# 5V_Converter.net
KiCad netlist of a schematic drawn in Altium Designer
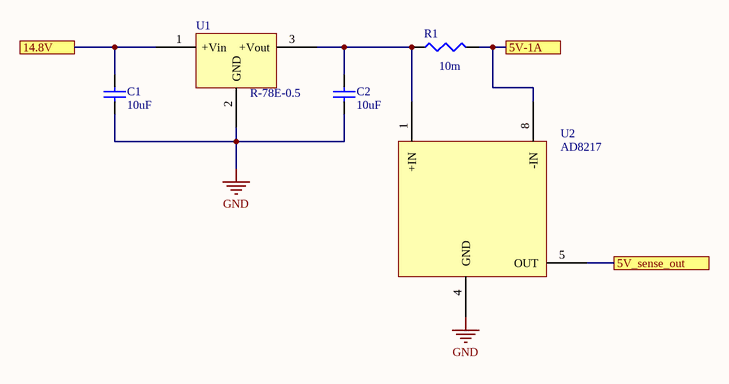
[diagram p0: 5V_Converter.SchDoc]

(export (version "E")
  (design (tool "Eeschema 10.0.6"))
  (components
    (comp (ref "C1")
      (value "10uF")
      (footprint "C1206")
      (description "Capacitor (Semiconductor SIM Model)")
      (fields (field (name "PUBLISHER") "Altium Limited"))
      (libsource (lib "Miscellaneous Devices") (part "Cap Semi"))
    )
    (comp (ref "C2")
      (value "10uF")
      (footprint "C1206")
      (description "Capacitor (Semiconductor SIM Model)")
      (fields (field (name "PUBLISHER") "Altium Limited"))
      (libsource (lib "Miscellaneous Devices") (part "Cap Semi"))
    )
    (comp (ref "R1")
      (value "10m")
      (footprint "J1-0603")
      (description "Resistor")
      (fields (field (name "Comment") "Res3") (field (name "PUBLISHER") "Altium Limited"))
      (libsource (lib "Miscellaneous Devices") (part "Res3"))
    )
    (comp (ref "U1")
      (value "R-78E-0.5")
      (footprint "R-78E-0.5")
      (description "DC/DC Converter")
      (libsource (lib "Integrated_Library") (part "R-78E-0.5"))
    )
    (comp (ref "U2")
      (value "AD8217")
      (footprint "AD8217")
      (description "Current Shunt Moniter")
      (libsource (lib "Integrated_Library") (part "AD8217"))
    )
  )
  (nets
    (net (code "1") (name "/5V-1A") (class "Default")
      (node (ref "R1") (pin "2") (pinfunction "2_2") (pintype "passive"))
      (node (ref "U2") (pin "8") (pinfunction "-IN_8") (pintype "passive"))
    )
    (net (code "2") (name "/5V_sense_out") (class "Default")
      (node (ref "U2") (pin "5") (pinfunction "OUT_5") (pintype "passive"))
    )
    (net (code "3") (name "/14.8V") (class "Default")
      (node (ref "C1") (pin "2") (pinfunction "2_2") (pintype "passive"))
      (node (ref "U1") (pin "1") (pinfunction "+Vin_1") (pintype "passive"))
    )
    (net (code "4") (name "GND") (class "Default")
      (node (ref "C1") (pin "1") (pinfunction "1_1") (pintype "passive"))
      (node (ref "C2") (pin "1") (pinfunction "1_1") (pintype "passive"))
      (node (ref "U1") (pin "2") (pinfunction "GND_2") (pintype "passive"))
      (node (ref "U2") (pin "4") (pinfunction "GND_4") (pintype "passive"))
    )
    (net (code "5") (name "Net-(U1-+Vout)") (class "Default")
      (node (ref "C2") (pin "2") (pinfunction "2_2") (pintype "passive"))
      (node (ref "R1") (pin "1") (pinfunction "1_1") (pintype "passive"))
      (node (ref "U1") (pin "3") (pinfunction "+Vout_3") (pintype "passive"))
      (node (ref "U2") (pin "1") (pinfunction "+IN_1") (pintype "passive"))
    )
  )
)
